# IO.net
KiCad netlist of a schematic drawn in Altium Designer
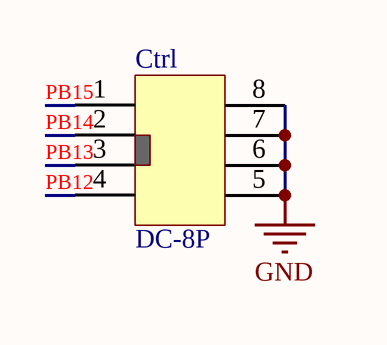
[diagram p0: IO.SchDoc]

(export (version "E")
  (design (tool "Eeschema 10.0.6"))
  (components
    (comp (ref "Ctrl") (value "DC-8P") (footprint "DC-8P") (libsource (lib "XuZhe") (part "DC-8P")))
  )
  (nets
    (net (code "1") (name "/PB12") (class "Default")
      (node (ref "Ctrl") (pin "4") (pinfunction "4_4") (pintype "passive"))
    )
    (net (code "2") (name "/PB13") (class "Default")
      (node (ref "Ctrl") (pin "3") (pinfunction "3_3") (pintype "passive"))
    )
    (net (code "3") (name "/PB14") (class "Default")
      (node (ref "Ctrl") (pin "2") (pinfunction "2_2") (pintype "passive"))
    )
    (net (code "4") (name "/PB15") (class "Default")
      (node (ref "Ctrl") (pin "1") (pinfunction "1_1") (pintype "passive"))
    )
    (net (code "5") (name "GND") (class "Default")
      (node (ref "Ctrl") (pin "5") (pinfunction "5_5") (pintype "passive"))
      (node (ref "Ctrl") (pin "6") (pinfunction "6_6") (pintype "passive"))
      (node (ref "Ctrl") (pin "7") (pinfunction "7_7") (pintype "passive"))
      (node (ref "Ctrl") (pin "8") (pinfunction "8_8") (pintype "passive"))
    )
  )
)
